# led_board_RGB-final.net
KiCad netlist of a schematic drawn in EAGLE
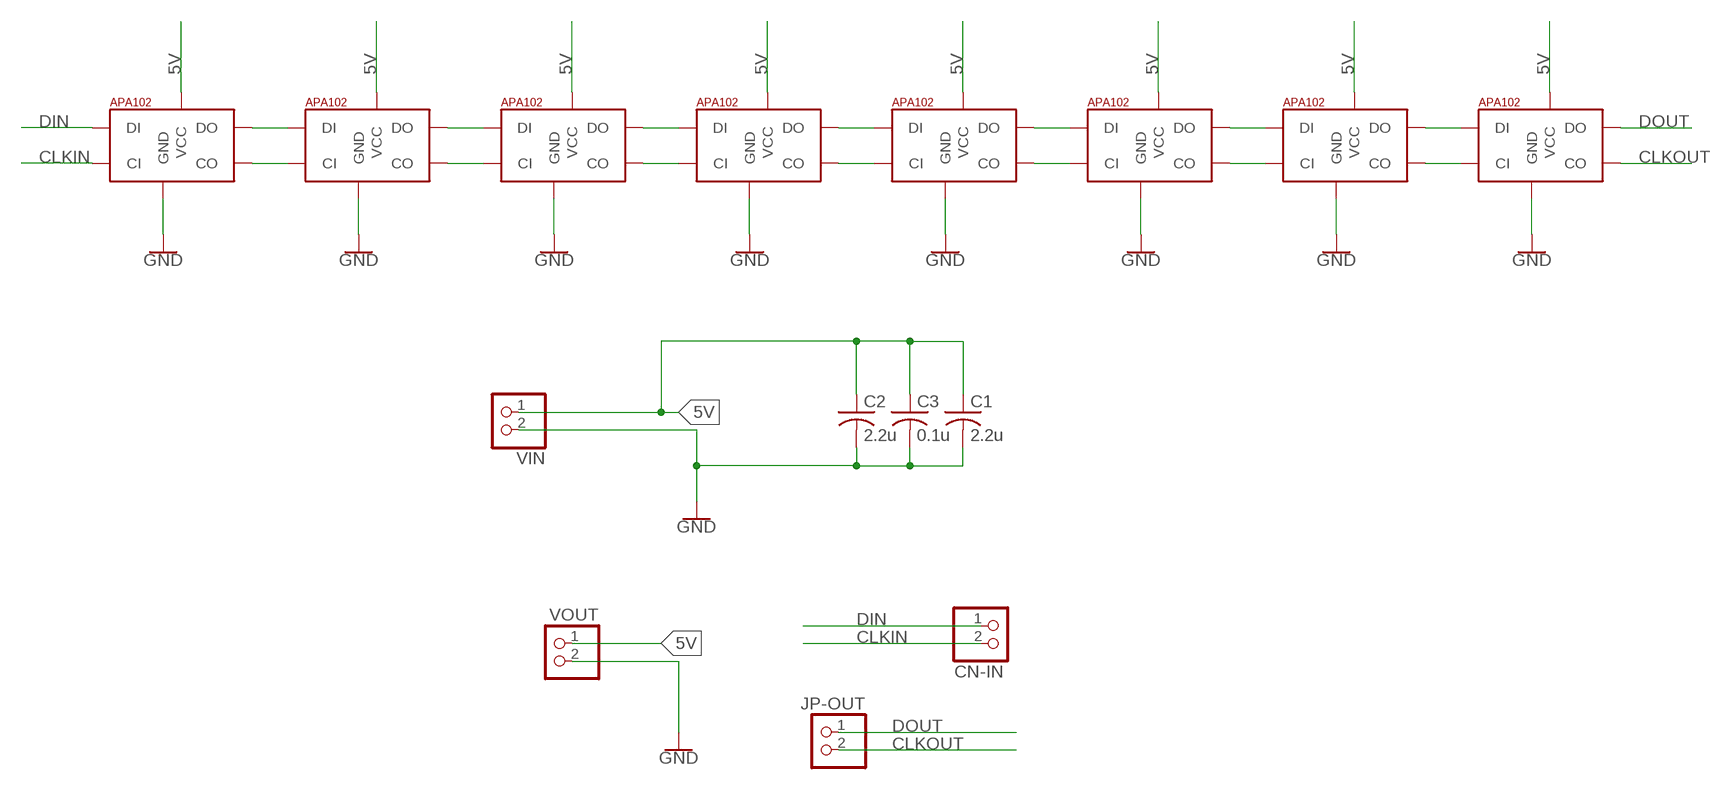
[diagram p0: schematic, sheet 1]

(export (version "E")
  (design (tool "Eeschema 10.0.6"))
  (components
    (comp (ref "C1")
      (value "2.2u")
      (footprint "eagle-import:C1206")
      (libsource (lib "eagle-import") (part "C-USC1206"))
    )
    (comp (ref "C2")
      (value "2.2u")
      (footprint "eagle-import:C1206")
      (libsource (lib "eagle-import") (part "C-USC1206"))
    )
    (comp (ref "C3")
      (value "0.1u")
      (footprint "eagle-import:C0805")
      (libsource (lib "eagle-import") (part "C-USC0805"))
    )
    (comp (ref "CN-IN")
      (value "JST_2PIN-THM-RA")
      (footprint "eagle-import:JST-PH-2-THM-RA")
      (libsource (lib "eagle-import") (part "JST_2PIN-THM-RA"))
    )
    (comp (ref "JP-OUT")
      (value "PINHD-1X2")
      (footprint "eagle-import:1X02")
      (libsource (lib "eagle-import") (part "PINHD-1X2"))
    )
    (comp (ref "U$1")
      (value "APA1022020")
      (footprint "eagle-import:APA102_2020")
      (libsource (lib "eagle-import") (part "APA1022020"))
    )
    (comp (ref "U$2")
      (value "APA1022020")
      (footprint "eagle-import:APA102_2020")
      (libsource (lib "eagle-import") (part "APA1022020"))
    )
    (comp (ref "U$3")
      (value "APA1022020")
      (footprint "eagle-import:APA102_2020")
      (libsource (lib "eagle-import") (part "APA1022020"))
    )
    (comp (ref "U$4")
      (value "APA1022020")
      (footprint "eagle-import:APA102_2020")
      (libsource (lib "eagle-import") (part "APA1022020"))
    )
    (comp (ref "U$5")
      (value "APA1022020")
      (footprint "eagle-import:APA102_2020")
      (libsource (lib "eagle-import") (part "APA1022020"))
    )
    (comp (ref "U$6")
      (value "APA1022020")
      (footprint "eagle-import:APA102_2020")
      (libsource (lib "eagle-import") (part "APA1022020"))
    )
    (comp (ref "U$7")
      (value "APA1022020")
      (footprint "eagle-import:APA102_2020")
      (libsource (lib "eagle-import") (part "APA1022020"))
    )
    (comp (ref "U$8")
      (value "APA1022020")
      (footprint "eagle-import:APA102_2020")
      (libsource (lib "eagle-import") (part "APA1022020"))
    )
    (comp (ref "VIN")
      (value "JST_2PIN-THM-RA")
      (footprint "eagle-import:JST-PH-2-THM-RA")
      (libsource (lib "eagle-import") (part "JST_2PIN-THM-RA"))
    )
    (comp (ref "VOUT")
      (value "PINHD-1X2")
      (footprint "eagle-import:1X02")
      (libsource (lib "eagle-import") (part "PINHD-1X2"))
    )
  )
  (nets
    (net (code "1") (name "/CLKIN") (class "Default")
      (node (ref "CN-IN") (pin "2") (pinfunction "1_2") (pintype "passive"))
      (node (ref "U$1") (pin "C_IN") (pinfunction "CI_C_IN") (pintype "bidirectional"))
    )
    (net (code "2") (name "/CLKOUT") (class "Default")
      (node (ref "JP-OUT") (pin "2") (pinfunction "2_2") (pintype "passive"))
      (node (ref "U$8") (pin "CL_OUT") (pinfunction "CO_CL_OUT") (pintype "bidirectional"))
    )
    (net (code "3") (name "/DIN") (class "Default")
      (node (ref "CN-IN") (pin "1") (pinfunction "2_1") (pintype "passive"))
      (node (ref "U$1") (pin "D_IN") (pinfunction "DI_D_IN") (pintype "bidirectional"))
    )
    (net (code "4") (name "/DOUT") (class "Default")
      (node (ref "JP-OUT") (pin "1") (pinfunction "1_1") (pintype "passive"))
      (node (ref "U$8") (pin "D_OUT") (pinfunction "DO_D_OUT") (pintype "bidirectional"))
    )
    (net (code "5") (name "5V") (class "Default")
      (node (ref "C1") (pin "1") (pinfunction "1_1") (pintype "passive"))
      (node (ref "C2") (pin "1") (pinfunction "1_1") (pintype "passive"))
      (node (ref "C3") (pin "1") (pinfunction "1_1") (pintype "passive"))
      (node (ref "U$1") (pin "V_CC") (pinfunction "VCC_V_CC") (pintype "bidirectional"))
      (node (ref "U$2") (pin "V_CC") (pinfunction "VCC_V_CC") (pintype "bidirectional"))
      (node (ref "U$3") (pin "V_CC") (pinfunction "VCC_V_CC") (pintype "bidirectional"))
      (node (ref "U$4") (pin "V_CC") (pinfunction "VCC_V_CC") (pintype "bidirectional"))
      (node (ref "U$5") (pin "V_CC") (pinfunction "VCC_V_CC") (pintype "bidirectional"))
      (node (ref "U$6") (pin "V_CC") (pinfunction "VCC_V_CC") (pintype "bidirectional"))
      (node (ref "U$7") (pin "V_CC") (pinfunction "VCC_V_CC") (pintype "bidirectional"))
      (node (ref "U$8") (pin "V_CC") (pinfunction "VCC_V_CC") (pintype "bidirectional"))
      (node (ref "VIN") (pin "1") (pinfunction "2_1") (pintype "passive"))
      (node (ref "VOUT") (pin "1") (pinfunction "1_1") (pintype "passive"))
    )
    (net (code "6") (name "GND") (class "Default")
      (node (ref "C1") (pin "2") (pinfunction "2_2") (pintype "passive"))
      (node (ref "C2") (pin "2") (pinfunction "2_2") (pintype "passive"))
      (node (ref "C3") (pin "2") (pinfunction "2_2") (pintype "passive"))
      (node (ref "U$1") (pin "GND") (pinfunction "GND_GND") (pintype "bidirectional"))
      (node (ref "U$2") (pin "GND") (pinfunction "GND_GND") (pintype "bidirectional"))
      (node (ref "U$3") (pin "GND") (pinfunction "GND_GND") (pintype "bidirectional"))
      (node (ref "U$4") (pin "GND") (pinfunction "GND_GND") (pintype "bidirectional"))
      (node (ref "U$5") (pin "GND") (pinfunction "GND_GND") (pintype "bidirectional"))
      (node (ref "U$6") (pin "GND") (pinfunction "GND_GND") (pintype "bidirectional"))
      (node (ref "U$7") (pin "GND") (pinfunction "GND_GND") (pintype "bidirectional"))
      (node (ref "U$8") (pin "GND") (pinfunction "GND_GND") (pintype "bidirectional"))
      (node (ref "VIN") (pin "2") (pinfunction "1_2") (pintype "passive"))
      (node (ref "VOUT") (pin "2") (pinfunction "2_2") (pintype "passive"))
    )
    (net (code "7") (name "Net-(U$1-CO)") (class "Default")
      (node (ref "U$1") (pin "CL_OUT") (pinfunction "CO_CL_OUT") (pintype "bidirectional"))
      (node (ref "U$2") (pin "C_IN") (pinfunction "CI_C_IN") (pintype "bidirectional"))
    )
    (net (code "8") (name "Net-(U$1-DO)") (class "Default")
      (node (ref "U$1") (pin "D_OUT") (pinfunction "DO_D_OUT") (pintype "bidirectional"))
      (node (ref "U$2") (pin "D_IN") (pinfunction "DI_D_IN") (pintype "bidirectional"))
    )
    (net (code "9") (name "Net-(U$2-CO)") (class "Default")
      (node (ref "U$2") (pin "CL_OUT") (pinfunction "CO_CL_OUT") (pintype "bidirectional"))
      (node (ref "U$3") (pin "C_IN") (pinfunction "CI_C_IN") (pintype "bidirectional"))
    )
    (net (code "10") (name "Net-(U$2-DO)") (class "Default")
      (node (ref "U$2") (pin "D_OUT") (pinfunction "DO_D_OUT") (pintype "bidirectional"))
      (node (ref "U$3") (pin "D_IN") (pinfunction "DI_D_IN") (pintype "bidirectional"))
    )
    (net (code "11") (name "Net-(U$3-CO)") (class "Default")
      (node (ref "U$3") (pin "CL_OUT") (pinfunction "CO_CL_OUT") (pintype "bidirectional"))
      (node (ref "U$4") (pin "C_IN") (pinfunction "CI_C_IN") (pintype "bidirectional"))
    )
    (net (code "12") (name "Net-(U$3-DO)") (class "Default")
      (node (ref "U$3") (pin "D_OUT") (pinfunction "DO_D_OUT") (pintype "bidirectional"))
      (node (ref "U$4") (pin "D_IN") (pinfunction "DI_D_IN") (pintype "bidirectional"))
    )
    (net (code "13") (name "Net-(U$4-CO)") (class "Default")
      (node (ref "U$4") (pin "CL_OUT") (pinfunction "CO_CL_OUT") (pintype "bidirectional"))
      (node (ref "U$5") (pin "C_IN") (pinfunction "CI_C_IN") (pintype "bidirectional"))
    )
    (net (code "14") (name "Net-(U$4-DO)") (class "Default")
      (node (ref "U$4") (pin "D_OUT") (pinfunction "DO_D_OUT") (pintype "bidirectional"))
      (node (ref "U$5") (pin "D_IN") (pinfunction "DI_D_IN") (pintype "bidirectional"))
    )
    (net (code "15") (name "Net-(U$5-CO)") (class "Default")
      (node (ref "U$5") (pin "CL_OUT") (pinfunction "CO_CL_OUT") (pintype "bidirectional"))
      (node (ref "U$6") (pin "C_IN") (pinfunction "CI_C_IN") (pintype "bidirectional"))
    )
    (net (code "16") (name "Net-(U$5-DO)") (class "Default")
      (node (ref "U$5") (pin "D_OUT") (pinfunction "DO_D_OUT") (pintype "bidirectional"))
      (node (ref "U$6") (pin "D_IN") (pinfunction "DI_D_IN") (pintype "bidirectional"))
    )
    (net (code "17") (name "Net-(U$6-CO)") (class "Default")
      (node (ref "U$6") (pin "CL_OUT") (pinfunction "CO_CL_OUT") (pintype "bidirectional"))
      (node (ref "U$7") (pin "C_IN") (pinfunction "CI_C_IN") (pintype "bidirectional"))
    )
    (net (code "18") (name "Net-(U$6-DO)") (class "Default")
      (node (ref "U$6") (pin "D_OUT") (pinfunction "DO_D_OUT") (pintype "bidirectional"))
      (node (ref "U$7") (pin "D_IN") (pinfunction "DI_D_IN") (pintype "bidirectional"))
    )
    (net (code "19") (name "Net-(U$7-CO)") (class "Default")
      (node (ref "U$7") (pin "CL_OUT") (pinfunction "CO_CL_OUT") (pintype "bidirectional"))
      (node (ref "U$8") (pin "C_IN") (pinfunction "CI_C_IN") (pintype "bidirectional"))
    )
    (net (code "20") (name "Net-(U$7-DO)") (class "Default")
      (node (ref "U$7") (pin "D_OUT") (pinfunction "DO_D_OUT") (pintype "bidirectional"))
      (node (ref "U$8") (pin "D_IN") (pinfunction "DI_D_IN") (pintype "bidirectional"))
    )
  )
)
